# LVRegulation.net
KiCad netlist of a schematic drawn in Altium Designer
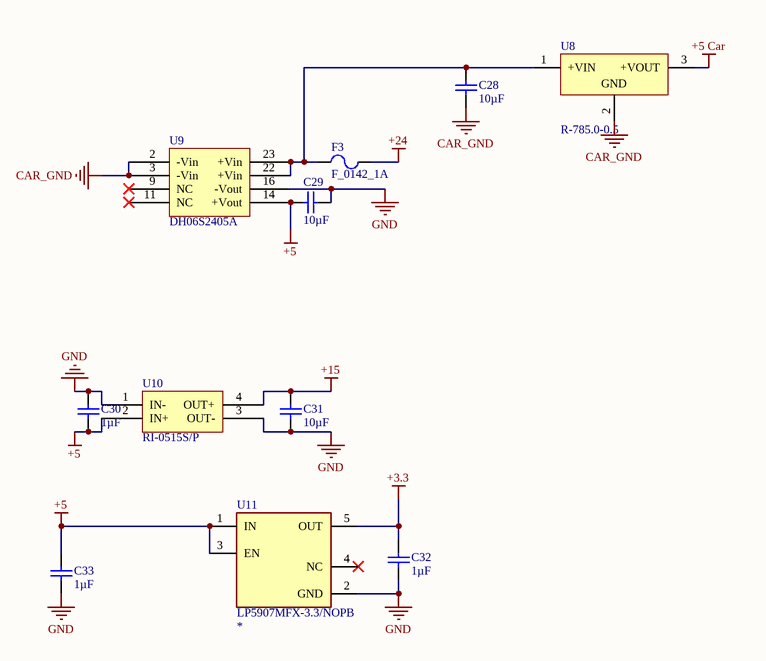
[diagram p0: LVRegulation.SchDoc]

(export (version "E")
  (design (tool "Eeschema 10.0.6"))
  (components
    (comp (ref "C28")
      (value "10µF")
      (footprint "1210_Capacitor")
      (description "Cap Cerem 10uF 10% 50V")
      (fields (field (name "TOLERANCE") "10%"))
      (libsource (lib "University of Minnesota - Solar Vehicle Project") (part "Cap"))
    )
    (comp (ref "C29")
      (value "10µF")
      (footprint "1210_Capacitor")
      (description "Cap Cerem 10uF 10% 50V")
      (fields (field (name "TOLERANCE") "10%"))
      (libsource (lib "University of Minnesota - Solar Vehicle Project") (part "Cap"))
    )
    (comp (ref "C30")
      (value "1µF")
      (footprint "0805_Capacitor")
      (description "CAP 0805 1uF 50V")
      (fields (field (name "TOLERANCE") "10%"))
      (libsource (lib "University of Minnesota - Solar Vehicle Project") (part "Cap"))
    )
    (comp (ref "C31")
      (value "10µF")
      (footprint "1210_Capacitor")
      (description "Cap Cerem 10uF 10% 50V")
      (fields (field (name "TOLERANCE") "10%"))
      (libsource (lib "University of Minnesota - Solar Vehicle Project") (part "Cap"))
    )
    (comp (ref "C32")
      (value "1µF")
      (footprint "0805_Capacitor")
      (description "CAP 0805 1uF 50V")
      (fields (field (name "TOLERANCE") "10%"))
      (libsource (lib "University of Minnesota - Solar Vehicle Project") (part "Cap"))
    )
    (comp (ref "C33")
      (value "1µF")
      (footprint "0805_Capacitor")
      (description "CAP 0805 1uF 50V")
      (fields (field (name "TOLERANCE") "10%"))
      (libsource (lib "University of Minnesota - Solar Vehicle Project") (part "Cap"))
    )
    (comp (ref "F3")
      (value "F_0142_1A")
      (footprint "0154_FUSE_HOLDER")
      (fields (field (name "SVP CREATOR") "Spencer Berglund"))
      (libsource (lib "University of Minnesota - Solar Vehicle Project") (part "F_0142_1A"))
    )
    (comp (ref "U8")
      (value "R-785.0-0.5")
      (footprint "REPO-R-78XX-3_V")
      (description "DC-DC Regulated Power Supply Module, 1 Output, 2.5W, Hybrid")
      (libsource (lib "University of Minnesota - Solar Vehicle Project") (part "REPO-R-78XX-3"))
    )
    (comp (ref "U9")
      (value "DH06S2405A")
      (footprint "DH06S2405A-Footprint-1")
      (description "DC/DC converter 18...75 VDC 5 VDC, DJ06S4805A, Delta-Electronics")
      (libsource (lib "University of Minnesota - Solar Vehicle Project") (part "DH06S2405A"))
    )
    (comp (ref "U10")
      (value "RI-0515S/P")
      (footprint "ROE-2405S-Footprint-1")
      (description "DC-DC Unregulated Power Supply Module, 1 Output, 2W, Hybrid")
      (libsource (lib "University of Minnesota - Solar Vehicle Project") (part "RI-0515S_P-Symbol-1"))
    )
    (comp (ref "U11")
      (value "LP5907MFX-3.3/NOPB")
      (footprint "FP-DBV0005A-MFG")
      (description "Fixed Positive LDO Regulator, 3.3V, 0.25V Dropout, PDSO5")
      (fields
        (field (name "MP") "LP5907MFX-3.0/NOPB")
        (field (name "ALTIUM_VALUE") "*")
        (field (name "MF") "Texas Instruments")
      )
      (libsource (lib "University of Minnesota - Solar Vehicle Project") (part "LP5907MFX-3.3/NOPB"))
    )
  )
  (nets
    (net (code "1") (name "+3.3") (class "Default")
      (node (ref "C32") (pin "2") (pinfunction "2_2") (pintype "passive"))
      (node (ref "U11") (pin "5") (pinfunction "OUT_5") (pintype "passive"))
    )
    (net (code "2") (name "+5") (class "Default")
      (node (ref "C29") (pin "1") (pinfunction "1_1") (pintype "passive"))
      (node (ref "C30") (pin "1") (pinfunction "1_1") (pintype "passive"))
      (node (ref "C33") (pin "2") (pinfunction "2_2") (pintype "passive"))
      (node (ref "U10") (pin "2") (pinfunction "IN+_2") (pintype "passive"))
      (node (ref "U11") (pin "1") (pinfunction "IN_1") (pintype "passive"))
      (node (ref "U11") (pin "3") (pinfunction "EN_3") (pintype "passive"))
      (node (ref "U9") (pin "14") (pinfunction "+Vout_14") (pintype "power_in"))
    )
    (net (code "3") (name "+5 Car") (class "Default")
      (node (ref "U8") (pin "3") (pinfunction "+VOUT_3") (pintype "power_in"))
    )
    (net (code "4") (name "+15") (class "Default")
      (node (ref "C31") (pin "2") (pinfunction "2_2") (pintype "passive"))
      (node (ref "U10") (pin "4") (pinfunction "OUT+_4") (pintype "passive"))
    )
    (net (code "5") (name "+24") (class "Default")
      (node (ref "F3") (pin "2") (pinfunction "2_2") (pintype "passive"))
    )
    (net (code "6") (name "CAR_GND") (class "Default")
      (node (ref "C28") (pin "1") (pinfunction "1_1") (pintype "passive"))
      (node (ref "U8") (pin "2") (pinfunction "GND_2") (pintype "power_in"))
      (node (ref "U9") (pin "2") (pinfunction "-Vin_2") (pintype "power_in"))
      (node (ref "U9") (pin "3") (pinfunction "-Vin_3") (pintype "power_in"))
    )
    (net (code "7") (name "GND") (class "Default")
      (node (ref "C29") (pin "2") (pinfunction "2_2") (pintype "passive"))
      (node (ref "C30") (pin "2") (pinfunction "2_2") (pintype "passive"))
      (node (ref "C31") (pin "1") (pinfunction "1_1") (pintype "passive"))
      (node (ref "C32") (pin "1") (pinfunction "1_1") (pintype "passive"))
      (node (ref "C33") (pin "1") (pinfunction "1_1") (pintype "passive"))
      (node (ref "U10") (pin "1") (pinfunction "IN-_1") (pintype "passive"))
      (node (ref "U10") (pin "3") (pinfunction "OUT-_3") (pintype "passive"))
      (node (ref "U11") (pin "2") (pinfunction "GND_2") (pintype "power_in"))
      (node (ref "U9") (pin "16") (pinfunction "-Vout_16") (pintype "power_in"))
    )
    (net (code "8") (name "Net-(U8-+VIN)") (class "Default")
      (node (ref "C28") (pin "2") (pinfunction "2_2") (pintype "passive"))
      (node (ref "F3") (pin "1") (pinfunction "1_1") (pintype "passive"))
      (node (ref "U8") (pin "1") (pinfunction "+VIN_1") (pintype "power_in"))
      (node (ref "U9") (pin "22") (pinfunction "+Vin_22") (pintype "power_in"))
      (node (ref "U9") (pin "23") (pinfunction "+Vin_23") (pintype "power_in"))
    )
    (net (code "9") (name "unconnected-(U9-NC-Pad9)") (class "Default")
      (node (ref "U9") (pin "9") (pinfunction "NC_9") (pintype "power_in+no_connect"))
    )
    (net (code "10") (name "unconnected-(U9-NC-Pad11)") (class "Default")
      (node (ref "U9") (pin "11") (pinfunction "NC_11") (pintype "power_in+no_connect"))
    )
    (net (code "11") (name "unconnected-(U11-NC-Pad4)") (class "Default")
      (node (ref "U11") (pin "4") (pinfunction "NC_4") (pintype "passive+no_connect"))
    )
  )
)
